# Sheet1.net
KiCad netlist of a schematic drawn in Altium Designer
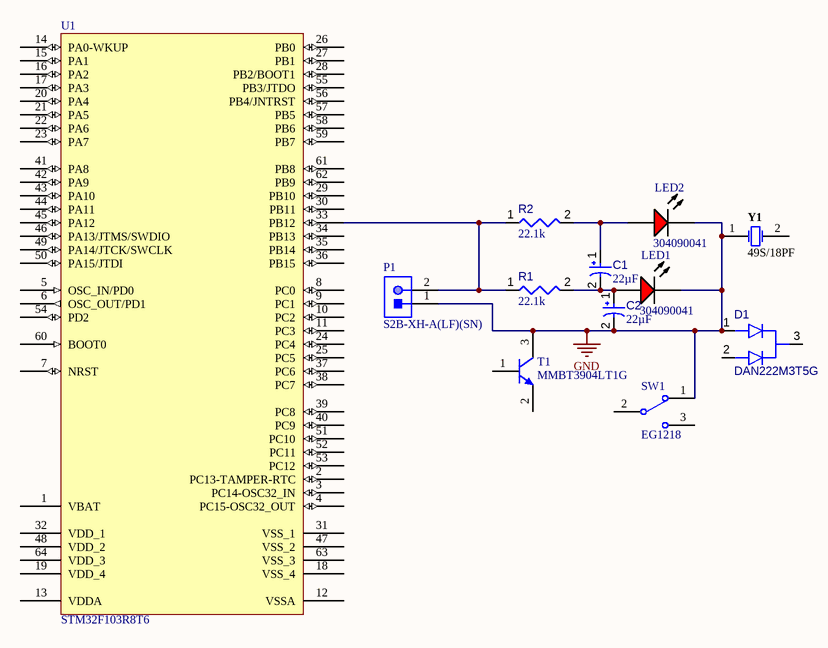
[diagram p0: Sheet1.SchDoc]

(export (version "E")
  (design (tool "Eeschema 10.0.6"))
  (components
    (comp (ref "C1")
      (value "22µF")
      (footprint "CAPPR55-200-1100X500X1200")
      (description "Aluminum Electrolytic Capacitor, 22 uF, +/- 20%, 50 V, -40 to 85 degC, 2-Pin THD, RoHS, Bulk")
      (fields (field (name "MANUFACTURER") "Panasonic") (field (name "TOLERANCE") "20%"))
      (libsource (lib "Ufscar - Universidade Federal de São Carlos") (part "CAP-P-2"))
    )
    (comp (ref "C2")
      (value "22µF")
      (footprint "CAPPR55-200-1100X500X1200")
      (description "Aluminum Electrolytic Capacitor, 22 uF, +/- 20%, 50 V, -40 to 85 degC, 2-Pin THD, RoHS, Bulk")
      (fields (field (name "MANUFACTURER") "Panasonic") (field (name "TOLERANCE") "20%"))
      (libsource (lib "Ufscar - Universidade Federal de São Carlos") (part "CAP-P-2"))
    )
    (comp (ref "D1")
      (value "DAN222M3T5G")
      (footprint "ROHM-SOT723-3_V")
      (description "Common Cathode Silicon Dual Switching Diodes, 3-Pin SOT-723, Pb-Free, Tape and Reel")
      (libsource (lib "Ufscar - Universidade Federal de São Carlos") (part "D-AAK-3"))
    )
    (comp (ref "LED1")
      (value "304090041")
      (footprint "LED-2P-2.28-3MM_A")
      (description "Red LED, 80 mW, 30 mA, -25 to 85 degC, 2-Pin THD")
      (fields (field (name "MANUFACTURER") "Shenzhen CGX"))
      (libsource (lib "Ufscar - Universidade Federal de São Carlos") (part "LED-RED-AK-2"))
    )
    (comp (ref "LED2")
      (value "304090041")
      (footprint "LED-2P-2.28-3MM_A")
      (description "Red LED, 80 mW, 30 mA, -25 to 85 degC, 2-Pin THD")
      (fields (field (name "MANUFACTURER") "Shenzhen CGX"))
      (libsource (lib "Ufscar - Universidade Federal de São Carlos") (part "LED-RED-AK-2"))
    )
    (comp (ref "P1")
      (value "S2B-XH-A(LF)(SN)")
      (footprint "JST-S2B-XH-A(LF)(SN)_V")
      (fields (field (name "MANUFACTURER") "JST"))
      (libsource (lib "Ufscar - Universidade Federal de São Carlos") (part "CN-1P-M-R2"))
    )
    (comp (ref "R1")
      (value "22.1k")
      (footprint "RESA60-630X240")
      (description "Axial Resistor, 22.1 KOhm, +/- 1%, 0.25 W, -55 to 155 degC, 2-Pin THD, RoHS, Bulk")
      (fields (field (name "TOLERANCE") "1%") (field (name "POWER") "250mW"))
      (libsource (lib "Ufscar - Universidade Federal de São Carlos") (part "RES-2"))
    )
    (comp (ref "R2")
      (value "22.1k")
      (footprint "RESA60-630X240")
      (description "Axial Resistor, 22.1 KOhm, +/- 1%, 0.25 W, -55 to 155 degC, 2-Pin THD, RoHS, Bulk")
      (fields (field (name "TOLERANCE") "1%") (field (name "POWER") "250mW"))
      (libsource (lib "Ufscar - Universidade Federal de São Carlos") (part "RES-2"))
    )
    (comp (ref "SW1")
      (value "EG1218")
      (footprint "ESWI-EG1218_V")
      (description "Slide Switch, SPDT, 500 V, -20 to 70 degC, 3-Pin THD, RoHS, Bulk")
      (fields (field (name "MANUFACTURER") "E-Switch"))
      (libsource (lib "Ufscar - Universidade Federal de São Carlos") (part "SW-SPDT-3_B"))
    )
    (comp (ref "T1")
      (value "MMBT3904LT1G")
      (footprint "ONSC-SOT-23-3-318-08_V")
      (fields (field (name "MANUFACTURER") "ON Semiconductor") (field (name "POWER") "225mW"))
      (libsource (lib "Ufscar - Universidade Federal de São Carlos") (part "ONSC-NPN-B1E2C3-3"))
    )
    (comp (ref "U1")
      (value "STM32F103R8T6")
      (footprint "TSQFP50P1200X1200X160-64M")
      (description "STM32 ARM-based 32-bit MCU with 64 Kbytes Flash, 64-pin LQFP, Industrial Temperature")
      (fields (field (name "PUBLISHER") "Altium Limited"))
      (libsource (lib "ST Microcontroller 32-Bit STM32") (part "STM32F103R8T6"))
    )
    (comp (ref "Y1")
      (value "49S/18PF")
      (footprint "JPY-49S-18PF")
      (description "Crystal, 16 MHz, +/-20 ppm, 18 pF, -20 to 70 degC, 2-Pin THD, RoHS")
      (fields (field (name "MANUFACTURER") "Shenzhen Jingpengyuan"))
      (libsource (lib "Ufscar - Universidade Federal de São Carlos") (part "XTAL-1-2-2"))
    )
  )
  (nets
    (net (code "1") (name "GND") (class "Default")
      (node (ref "C2") (pin "2") (pinfunction "2_2") (pintype "passive"))
      (node (ref "D1") (pin "1") (pinfunction "A1_1") (pintype "passive"))
      (node (ref "LED1") (pin "2") (pinfunction "K_2") (pintype "passive"))
      (node (ref "LED2") (pin "2") (pinfunction "K_2") (pintype "passive"))
      (node (ref "P1") (pin "1") (pinfunction "1_1") (pintype "passive"))
      (node (ref "SW1") (pin "1") (pinfunction "1_1") (pintype "passive"))
      (node (ref "T1") (pin "3") (pinfunction "C_3") (pintype "passive"))
      (node (ref "Y1") (pin "1") (pinfunction "1_1") (pintype "passive"))
    )
    (net (code "2") (name "Net-(LED1-A)") (class "Default")
      (node (ref "C1") (pin "2") (pinfunction "2_2") (pintype "passive"))
      (node (ref "C2") (pin "1") (pinfunction "1_1") (pintype "passive"))
      (node (ref "LED1") (pin "1") (pinfunction "A_1") (pintype "passive"))
      (node (ref "R1") (pin "2") (pinfunction "2_2") (pintype "passive"))
    )
    (net (code "3") (name "Net-(LED2-A)") (class "Default")
      (node (ref "C1") (pin "1") (pinfunction "1_1") (pintype "passive"))
      (node (ref "LED2") (pin "1") (pinfunction "A_1") (pintype "passive"))
      (node (ref "R2") (pin "2") (pinfunction "2_2") (pintype "passive"))
    )
    (net (code "4") (name "Net-(U1-PB12)") (class "Default")
      (node (ref "P1") (pin "2") (pinfunction "2_2") (pintype "passive"))
      (node (ref "R1") (pin "1") (pinfunction "1_1") (pintype "passive"))
      (node (ref "R2") (pin "1") (pinfunction "1_1") (pintype "passive"))
      (node (ref "U1") (pin "33") (pinfunction "PB12_33") (pintype "bidirectional"))
    )
    (net (code "5") (name "unconnected-(D1-A2-Pad2)") (class "Default")
      (node (ref "D1") (pin "2") (pinfunction "A2_2") (pintype "passive"))
    )
    (net (code "6") (name "unconnected-(D1-K-Pad3)") (class "Default")
      (node (ref "D1") (pin "3") (pinfunction "K_3") (pintype "passive"))
    )
    (net (code "7") (name "unconnected-(SW1-COM-Pad2)") (class "Default")
      (node (ref "SW1") (pin "2") (pinfunction "COM_2") (pintype "passive"))
    )
    (net (code "8") (name "unconnected-(SW1-Pad3)") (class "Default")
      (node (ref "SW1") (pin "3") (pinfunction "3_3") (pintype "passive"))
    )
    (net (code "9") (name "unconnected-(T1-B-Pad1)") (class "Default")
      (node (ref "T1") (pin "1") (pinfunction "B_1") (pintype "passive"))
    )
    (net (code "10") (name "unconnected-(T1-E-Pad2)") (class "Default")
      (node (ref "T1") (pin "2") (pinfunction "E_2") (pintype "passive"))
    )
    (net (code "11") (name "unconnected-(U1-BOOT0-Pad60)") (class "Default")
      (node (ref "U1") (pin "60") (pinfunction "BOOT0_60") (pintype "input"))
    )
    (net (code "12") (name "unconnected-(U1-NRST-Pad7)") (class "Default")
      (node (ref "U1") (pin "7") (pinfunction "NRST_7") (pintype "bidirectional"))
    )
    (net (code "13") (name "unconnected-(U1-OSC_IN{slash}PD0-Pad5)") (class "Default")
      (node (ref "U1") (pin "5") (pinfunction "OSC_IN/PD0_5") (pintype "input"))
    )
    (net (code "14") (name "unconnected-(U1-OSC_OUT{slash}PD1-Pad6)") (class "Default")
      (node (ref "U1") (pin "6") (pinfunction "OSC_OUT/PD1_6") (pintype "output"))
    )
    (net (code "15") (name "unconnected-(U1-PA0-WKUP-Pad14)") (class "Default")
      (node (ref "U1") (pin "14") (pinfunction "PA0-WKUP_14") (pintype "bidirectional"))
    )
    (net (code "16") (name "unconnected-(U1-PA1-Pad15)") (class "Default")
      (node (ref "U1") (pin "15") (pinfunction "PA1_15") (pintype "bidirectional"))
    )
    (net (code "17") (name "unconnected-(U1-PA2-Pad16)") (class "Default")
      (node (ref "U1") (pin "16") (pinfunction "PA2_16") (pintype "bidirectional"))
    )
    (net (code "18") (name "unconnected-(U1-PA3-Pad17)") (class "Default")
      (node (ref "U1") (pin "17") (pinfunction "PA3_17") (pintype "bidirectional"))
    )
    (net (code "19") (name "unconnected-(U1-PA4-Pad20)") (class "Default")
      (node (ref "U1") (pin "20") (pinfunction "PA4_20") (pintype "bidirectional"))
    )
    (net (code "20") (name "unconnected-(U1-PA5-Pad21)") (class "Default")
      (node (ref "U1") (pin "21") (pinfunction "PA5_21") (pintype "bidirectional"))
    )
    (net (code "21") (name "unconnected-(U1-PA6-Pad22)") (class "Default")
      (node (ref "U1") (pin "22") (pinfunction "PA6_22") (pintype "bidirectional"))
    )
    (net (code "22") (name "unconnected-(U1-PA7-Pad23)") (class "Default")
      (node (ref "U1") (pin "23") (pinfunction "PA7_23") (pintype "bidirectional"))
    )
    (net (code "23") (name "unconnected-(U1-PA8-Pad41)") (class "Default")
      (node (ref "U1") (pin "41") (pinfunction "PA8_41") (pintype "bidirectional"))
    )
    (net (code "24") (name "unconnected-(U1-PA9-Pad42)") (class "Default")
      (node (ref "U1") (pin "42") (pinfunction "PA9_42") (pintype "bidirectional"))
    )
    (net (code "25") (name "unconnected-(U1-PA10-Pad43)") (class "Default")
      (node (ref "U1") (pin "43") (pinfunction "PA10_43") (pintype "bidirectional"))
    )
    (net (code "26") (name "unconnected-(U1-PA11-Pad44)") (class "Default")
      (node (ref "U1") (pin "44") (pinfunction "PA11_44") (pintype "bidirectional"))
    )
    (net (code "27") (name "unconnected-(U1-PA12-Pad45)") (class "Default")
      (node (ref "U1") (pin "45") (pinfunction "PA12_45") (pintype "bidirectional"))
    )
    (net (code "28") (name "unconnected-(U1-PA13{slash}JTMS{slash}SWDIO-Pad46)") (class "Default")
      (node (ref "U1") (pin "46") (pinfunction "PA13/JTMS/SWDIO_46") (pintype "bidirectional"))
    )
    (net (code "29") (name "unconnected-(U1-PA14{slash}JTCK{slash}SWCLK-Pad49)") (class "Default")
      (node (ref "U1") (pin "49") (pinfunction "PA14/JTCK/SWCLK_49") (pintype "bidirectional"))
    )
    (net (code "30") (name "unconnected-(U1-PA15{slash}JTDI-Pad50)") (class "Default")
      (node (ref "U1") (pin "50") (pinfunction "PA15/JTDI_50") (pintype "bidirectional"))
    )
    (net (code "31") (name "unconnected-(U1-PB0-Pad26)") (class "Default")
      (node (ref "U1") (pin "26") (pinfunction "PB0_26") (pintype "bidirectional"))
    )
    (net (code "32") (name "unconnected-(U1-PB1-Pad27)") (class "Default")
      (node (ref "U1") (pin "27") (pinfunction "PB1_27") (pintype "bidirectional"))
    )
    (net (code "33") (name "unconnected-(U1-PB2{slash}BOOT1-Pad28)") (class "Default")
      (node (ref "U1") (pin "28") (pinfunction "PB2/BOOT1_28") (pintype "bidirectional"))
    )
    (net (code "34") (name "unconnected-(U1-PB3{slash}JTDO-Pad55)") (class "Default")
      (node (ref "U1") (pin "55") (pinfunction "PB3/JTDO_55") (pintype "bidirectional"))
    )
    (net (code "35") (name "unconnected-(U1-PB4{slash}JNTRST-Pad56)") (class "Default")
      (node (ref "U1") (pin "56") (pinfunction "PB4/JNTRST_56") (pintype "bidirectional"))
    )
    (net (code "36") (name "unconnected-(U1-PB5-Pad57)") (class "Default")
      (node (ref "U1") (pin "57") (pinfunction "PB5_57") (pintype "bidirectional"))
    )
    (net (code "37") (name "unconnected-(U1-PB6-Pad58)") (class "Default")
      (node (ref "U1") (pin "58") (pinfunction "PB6_58") (pintype "bidirectional"))
    )
    (net (code "38") (name "unconnected-(U1-PB7-Pad59)") (class "Default")
      (node (ref "U1") (pin "59") (pinfunction "PB7_59") (pintype "bidirectional"))
    )
    (net (code "39") (name "unconnected-(U1-PB8-Pad61)") (class "Default")
      (node (ref "U1") (pin "61") (pinfunction "PB8_61") (pintype "bidirectional"))
    )
    (net (code "40") (name "unconnected-(U1-PB9-Pad62)") (class "Default")
      (node (ref "U1") (pin "62") (pinfunction "PB9_62") (pintype "bidirectional"))
    )
    (net (code "41") (name "unconnected-(U1-PB10-Pad29)") (class "Default")
      (node (ref "U1") (pin "29") (pinfunction "PB10_29") (pintype "bidirectional"))
    )
    (net (code "42") (name "unconnected-(U1-PB11-Pad30)") (class "Default")
      (node (ref "U1") (pin "30") (pinfunction "PB11_30") (pintype "bidirectional"))
    )
    (net (code "43") (name "unconnected-(U1-PB13-Pad34)") (class "Default")
      (node (ref "U1") (pin "34") (pinfunction "PB13_34") (pintype "bidirectional"))
    )
    (net (code "44") (name "unconnected-(U1-PB14-Pad35)") (class "Default")
      (node (ref "U1") (pin "35") (pinfunction "PB14_35") (pintype "bidirectional"))
    )
    (net (code "45") (name "unconnected-(U1-PB15-Pad36)") (class "Default")
      (node (ref "U1") (pin "36") (pinfunction "PB15_36") (pintype "bidirectional"))
    )
    (net (code "46") (name "unconnected-(U1-PC0-Pad8)") (class "Default")
      (node (ref "U1") (pin "8") (pinfunction "PC0_8") (pintype "bidirectional"))
    )
    (net (code "47") (name "unconnected-(U1-PC1-Pad9)") (class "Default")
      (node (ref "U1") (pin "9") (pinfunction "PC1_9") (pintype "bidirectional"))
    )
    (net (code "48") (name "unconnected-(U1-PC2-Pad10)") (class "Default")
      (node (ref "U1") (pin "10") (pinfunction "PC2_10") (pintype "bidirectional"))
    )
    (net (code "49") (name "unconnected-(U1-PC3-Pad11)") (class "Default")
      (node (ref "U1") (pin "11") (pinfunction "PC3_11") (pintype "bidirectional"))
    )
    (net (code "50") (name "unconnected-(U1-PC4-Pad24)") (class "Default")
      (node (ref "U1") (pin "24") (pinfunction "PC4_24") (pintype "bidirectional"))
    )
    (net (code "51") (name "unconnected-(U1-PC5-Pad25)") (class "Default")
      (node (ref "U1") (pin "25") (pinfunction "PC5_25") (pintype "bidirectional"))
    )
    (net (code "52") (name "unconnected-(U1-PC6-Pad37)") (class "Default")
      (node (ref "U1") (pin "37") (pinfunction "PC6_37") (pintype "bidirectional"))
    )
    (net (code "53") (name "unconnected-(U1-PC7-Pad38)") (class "Default")
      (node (ref "U1") (pin "38") (pinfunction "PC7_38") (pintype "bidirectional"))
    )
    (net (code "54") (name "unconnected-(U1-PC8-Pad39)") (class "Default")
      (node (ref "U1") (pin "39") (pinfunction "PC8_39") (pintype "bidirectional"))
    )
    (net (code "55") (name "unconnected-(U1-PC9-Pad40)") (class "Default")
      (node (ref "U1") (pin "40") (pinfunction "PC9_40") (pintype "bidirectional"))
    )
    (net (code "56") (name "unconnected-(U1-PC10-Pad51)") (class "Default")
      (node (ref "U1") (pin "51") (pinfunction "PC10_51") (pintype "bidirectional"))
    )
    (net (code "57") (name "unconnected-(U1-PC11-Pad52)") (class "Default")
      (node (ref "U1") (pin "52") (pinfunction "PC11_52") (pintype "bidirectional"))
    )
    (net (code "58") (name "unconnected-(U1-PC12-Pad53)") (class "Default")
      (node (ref "U1") (pin "53") (pinfunction "PC12_53") (pintype "bidirectional"))
    )
    (net (code "59") (name "unconnected-(U1-PC13-TAMPER-RTC-Pad2)") (class "Default")
      (node (ref "U1") (pin "2") (pinfunction "PC13-TAMPER-RTC_2") (pintype "bidirectional"))
    )
    (net (code "60") (name "unconnected-(U1-PC14-OSC32_IN-Pad3)") (class "Default")
      (node (ref "U1") (pin "3") (pinfunction "PC14-OSC32_IN_3") (pintype "bidirectional"))
    )
    (net (code "61") (name "unconnected-(U1-PC15-OSC32_OUT-Pad4)") (class "Default")
      (node (ref "U1") (pin "4") (pinfunction "PC15-OSC32_OUT_4") (pintype "bidirectional"))
    )
    (net (code "62") (name "unconnected-(U1-PD2-Pad54)") (class "Default")
      (node (ref "U1") (pin "54") (pinfunction "PD2_54") (pintype "bidirectional"))
    )
    (net (code "63") (name "unconnected-(U1-VBAT-Pad1)") (class "Default")
      (node (ref "U1") (pin "1") (pinfunction "VBAT_1") (pintype "power_in"))
    )
    (net (code "64") (name "unconnected-(U1-VDDA-Pad13)") (class "Default")
      (node (ref "U1") (pin "13") (pinfunction "VDDA_13") (pintype "power_in"))
    )
    (net (code "65") (name "unconnected-(U1-VDD_1-Pad32)") (class "Default")
      (node (ref "U1") (pin "32") (pinfunction "VDD_1_32") (pintype "power_in"))
    )
    (net (code "66") (name "unconnected-(U1-VDD_2-Pad48)") (class "Default")
      (node (ref "U1") (pin "48") (pinfunction "VDD_2_48") (pintype "power_in"))
    )
    (net (code "67") (name "unconnected-(U1-VDD_3-Pad64)") (class "Default")
      (node (ref "U1") (pin "64") (pinfunction "VDD_3_64") (pintype "power_in"))
    )
    (net (code "68") (name "unconnected-(U1-VDD_4-Pad19)") (class "Default")
      (node (ref "U1") (pin "19") (pinfunction "VDD_4_19") (pintype "power_in"))
    )
    (net (code "69") (name "unconnected-(U1-VSSA-Pad12)") (class "Default")
      (node (ref "U1") (pin "12") (pinfunction "VSSA_12") (pintype "power_in"))
    )
    (net (code "70") (name "unconnected-(U1-VSS_1-Pad31)") (class "Default")
      (node (ref "U1") (pin "31") (pinfunction "VSS_1_31") (pintype "power_in"))
    )
    (net (code "71") (name "unconnected-(U1-VSS_2-Pad47)") (class "Default")
      (node (ref "U1") (pin "47") (pinfunction "VSS_2_47") (pintype "power_in"))
    )
    (net (code "72") (name "unconnected-(U1-VSS_3-Pad63)") (class "Default")
      (node (ref "U1") (pin "63") (pinfunction "VSS_3_63") (pintype "power_in"))
    )
    (net (code "73") (name "unconnected-(U1-VSS_4-Pad18)") (class "Default")
      (node (ref "U1") (pin "18") (pinfunction "VSS_4_18") (pintype "power_in"))
    )
    (net (code "74") (name "unconnected-(Y1-Pad2)") (class "Default")
      (node (ref "Y1") (pin "2") (pinfunction "2_2") (pintype "passive"))
    )
  )
)
